# Siguino.net
KiCad netlist of a schematic drawn in EAGLE
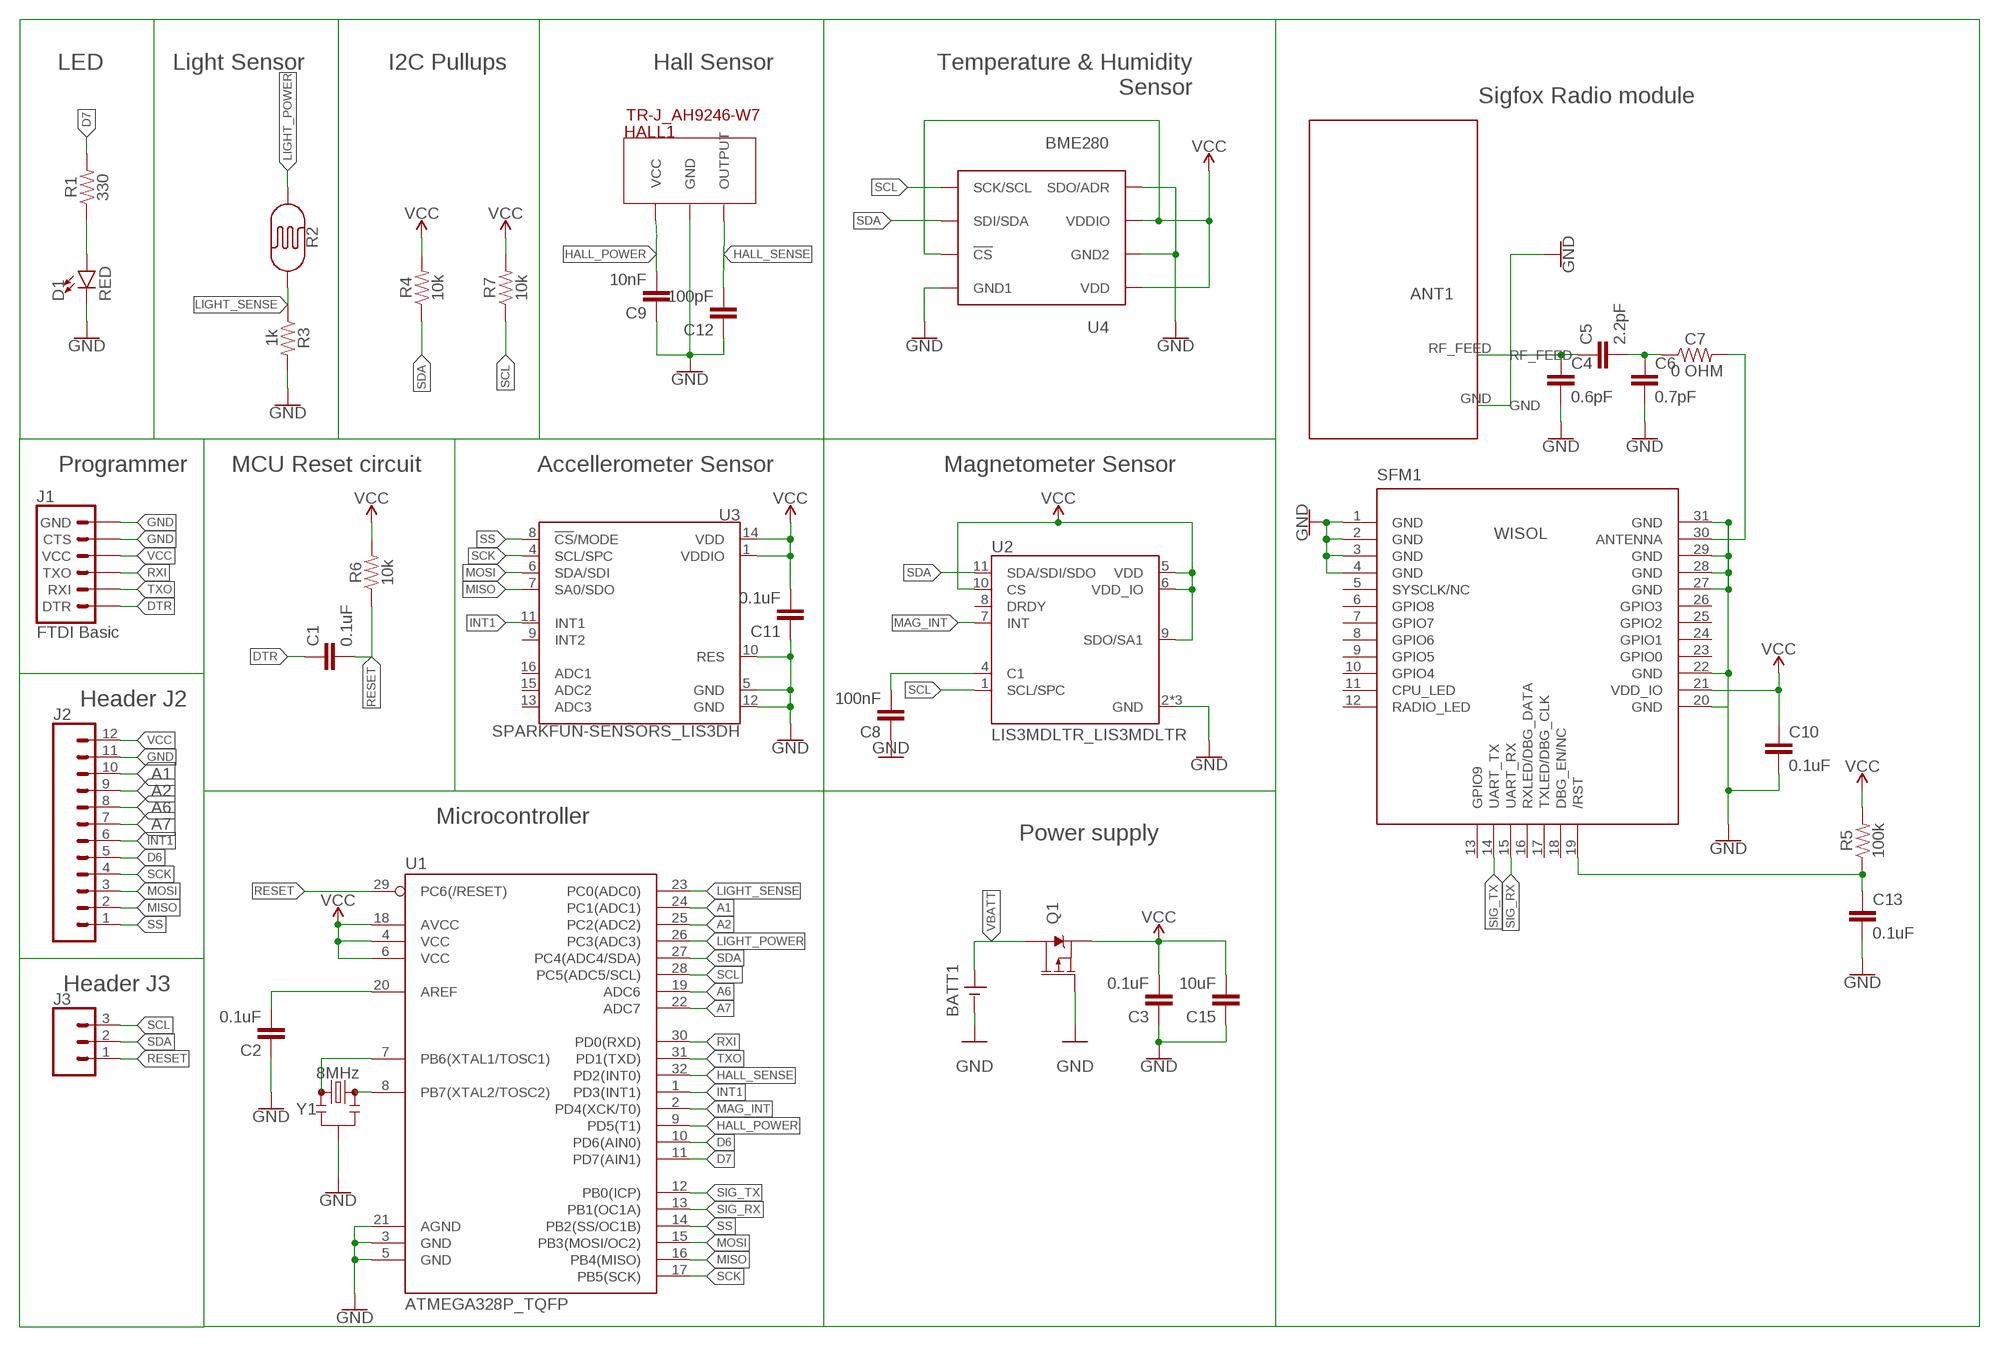
[diagram p0: schematic, sheet 1]

(export (version "E")
  (design (tool "Eeschema 10.0.6"))
  (components
    (comp (ref "ANT1")
      (value "PROOB471")
      (footprint "eagle-import:ONBOARD_SMD_2400")
      (libsource (lib "eagle-import") (part "PRO-OB-512ONBOARD"))
    )
    (comp (ref "BATT1")
      (value "SPARKFUN-BATTERIES_CR2-BATTERY-HOLDERPTH")
      (footprint "eagle-import:SPARKFUN-BATTERIES_BATTERYHOLDER-CR2")
      (libsource (lib "eagle-import") (part "SPARKFUN-BATTERIES_CR2-BATTERY-HOLDERPTH"))
    )
    (comp (ref "C1")
      (value "0.1uF")
      (footprint "eagle-import:0603")
      (libsource (lib "eagle-import") (part "0.1UF-0603-25V-5%"))
    )
    (comp (ref "C2")
      (value "0.1uF")
      (footprint "eagle-import:0603")
      (libsource (lib "eagle-import") (part "0.1UF-0603-25V-5%"))
    )
    (comp (ref "C3")
      (value "0.1uF")
      (footprint "eagle-import:0603")
      (libsource (lib "eagle-import") (part "0.1UF-0603-25V-5%"))
    )
    (comp (ref "C4")
      (value "0.6pF")
      (footprint "eagle-import:0402")
      (libsource (lib "eagle-import") (part "0.8PF-0402-50V-0.1PF"))
    )
    (comp (ref "C5")
      (value "2.2pF")
      (footprint "eagle-import:0402")
      (libsource (lib "eagle-import") (part "0.8PF-0402-50V-0.1PF"))
    )
    (comp (ref "C6")
      (value "0.7pF")
      (footprint "eagle-import:0402")
      (libsource (lib "eagle-import") (part "0.8PF-0402-50V-0.1PF"))
    )
    (comp (ref "C7")
      (value "0 OHM")
      (footprint "eagle-import:0402")
      (libsource (lib "eagle-import") (part "RESISTOR0402"))
    )
    (comp (ref "C8")
      (value "100nF")
      (footprint "eagle-import:0603")
      (libsource (lib "eagle-import") (part "0.1UF-0603-25V-5%"))
    )
    (comp (ref "C9")
      (value "10nF")
      (footprint "eagle-import:0603")
      (libsource (lib "eagle-import") (part "10NF-0603-50V-10%"))
    )
    (comp (ref "C10")
      (value "0.1uF")
      (footprint "eagle-import:0603")
      (libsource (lib "eagle-import") (part "0.1UF-0603-25V-(+80/-20%)"))
    )
    (comp (ref "C11")
      (value "0.1uF")
      (footprint "eagle-import:0603")
      (libsource (lib "eagle-import") (part "0.1UF-0603-25V-5%"))
    )
    (comp (ref "C12")
      (value "100pF")
      (footprint "eagle-import:0603")
      (libsource (lib "eagle-import") (part "100PF-0603-50V-5%"))
    )
    (comp (ref "C13")
      (value "0.1uF")
      (footprint "eagle-import:0603")
      (libsource (lib "eagle-import") (part "0.1UF-0603-25V-(+80/-20%)"))
    )
    (comp (ref "C15")
      (value "10uF")
      (footprint "eagle-import:0603")
      (libsource (lib "eagle-import") (part "10UF-0603-6.3V-20%"))
    )
    (comp (ref "D1")
      (value "RED")
      (footprint "eagle-import:LED-0603")
      (libsource (lib "eagle-import") (part "LED-RED0603"))
    )
    (comp (ref "HALL1")
      (value "TR-J_AH9246-W7")
      (footprint "eagle-import:TR-J_SC-59")
      (libsource (lib "eagle-import") (part "TR-J_AH9246-W7"))
    )
    (comp (ref "J1")
      (value "FTDI Basic")
      (footprint "eagle-import:1X06")
      (libsource (lib "eagle-import") (part "6_PIN_SERIAL_TARGET"))
    )
    (comp (ref "J2")
      (value "CONN_12")
      (footprint "eagle-import:1X12")
      (libsource (lib "eagle-import") (part "CONN_12"))
    )
    (comp (ref "J3")
      (value "CONN_03")
      (footprint "eagle-import:1X03")
      (libsource (lib "eagle-import") (part "CONN_03"))
    )
    (comp (ref "Q1")
      (value "MOSFET P-CH 20V 5.3A SOT-23")
      (footprint "eagle-import:SOT23-3")
      (libsource (lib "eagle-import") (part "MOSFET_PCHSI2323DDS"))
    )
    (comp (ref "R1")
      (value "330")
      (footprint "eagle-import:0603")
      (libsource (lib "eagle-import") (part "330OHM-0603-1/10W-1%"))
    )
    (comp (ref "R2")
      (value "PHOTOCELLPTH")
      (footprint "eagle-import:PHOTOCELL")
      (libsource (lib "eagle-import") (part "PHOTOCELLPTH"))
    )
    (comp (ref "R3")
      (value "1k")
      (footprint "eagle-import:0603")
      (libsource (lib "eagle-import") (part "1KOHM-0603-1/10W-1%"))
    )
    (comp (ref "R4")
      (value "10k")
      (footprint "eagle-import:0603")
      (libsource (lib "eagle-import") (part "10KOHM-0603-1/10W-1%"))
    )
    (comp (ref "R5")
      (value "100k")
      (footprint "eagle-import:0603")
      (libsource (lib "eagle-import") (part "100KOHM-0603-1/10W-1%"))
    )
    (comp (ref "R6")
      (value "10k")
      (footprint "eagle-import:0603")
      (libsource (lib "eagle-import") (part "10KOHM-0603-1/10W-1%"))
    )
    (comp (ref "R7")
      (value "10k")
      (footprint "eagle-import:0603")
      (libsource (lib "eagle-import") (part "10KOHM-0603-1/10W-1%"))
    )
    (comp (ref "SFM1")
      (value "WISOL_WSSFM10HANDSOLDER")
      (footprint "eagle-import:WISOL_WSSFM10")
      (libsource (lib "eagle-import") (part "WISOL_WSSFM10HANDSOLDER"))
    )
    (comp (ref "U1")
      (value "ATMEGA328P_TQFP")
      (footprint "eagle-import:TQFP32-08")
      (libsource (lib "eagle-import") (part "ATMEGA328P_TQFP"))
    )
    (comp (ref "U2")
      (value "LIS3MDLTR_LIS3MDLTR")
      (footprint "eagle-import:LIS3MDLTR_LGA12R50P4X4_200X200X100")
      (fields
        (field (name "DIGI-KEY_PART_NUMBER") "497-13892-1-ND")
        (field (name "MF") "STMicroelectronics")
        (field (name "MP") "LIS3MDLTR")
      )
      (libsource (lib "eagle-import") (part "LIS3MDLTR_LIS3MDLTR"))
    )
    (comp (ref "U3")
      (value "SPARKFUN-SENSORS_LIS3DH")
      (footprint "eagle-import:SPARKFUN-SENSORS_LGA-16-3X3")
      (libsource (lib "eagle-import") (part "SPARKFUN-SENSORS_LIS3DH"))
    )
    (comp (ref "U4")
      (value "BME280")
      (footprint "eagle-import:BME280COMPONENTLIBRARY_BME280_LGA")
      (libsource (lib "eagle-import") (part "BME280COMPONENTLIBRARY_BME280"))
    )
    (comp (ref "Y1")
      (value "8MHz")
      (footprint "eagle-import:RESONATOR-SMD-3.2X1.3")
      (libsource (lib "eagle-import") (part "RESONATOR-8MHZSMD_3.2X1.3"))
    )
  )
  (nets
    (net (code "1") (name "A1") (class "Default")
      (node (ref "J2") (pin "10") (pinfunction "10_10") (pintype "passive"))
      (node (ref "U1") (pin "24") (pinfunction "PC1(ADC1)_24") (pintype "bidirectional"))
    )
    (net (code "2") (name "A2") (class "Default")
      (node (ref "J2") (pin "9") (pinfunction "9_9") (pintype "passive"))
      (node (ref "U1") (pin "25") (pinfunction "PC2(ADC2)_25") (pintype "bidirectional"))
    )
    (net (code "3") (name "A6") (class "Default")
      (node (ref "J2") (pin "8") (pinfunction "8_8") (pintype "passive"))
      (node (ref "U1") (pin "19") (pinfunction "ADC6_19") (pintype "bidirectional"))
    )
    (net (code "4") (name "A7") (class "Default")
      (node (ref "J2") (pin "7") (pinfunction "7_7") (pintype "passive"))
      (node (ref "U1") (pin "22") (pinfunction "ADC7_22") (pintype "bidirectional"))
    )
    (net (code "5") (name "D6") (class "Default")
      (node (ref "J2") (pin "5") (pinfunction "5_5") (pintype "passive"))
      (node (ref "U1") (pin "10") (pinfunction "PD6(AIN0)_10") (pintype "bidirectional"))
    )
    (net (code "6") (name "D7") (class "Default")
      (node (ref "R1") (pin "2") (pinfunction "2_2") (pintype "passive"))
      (node (ref "U1") (pin "11") (pinfunction "PD7(AIN1)_11") (pintype "bidirectional"))
    )
    (net (code "7") (name "DTR") (class "Default")
      (node (ref "C1") (pin "1") (pinfunction "1_1") (pintype "passive"))
      (node (ref "J1") (pin "1") (pinfunction "DTR_1") (pintype "passive"))
    )
    (net (code "8") (name "GND") (class "Default")
      (node (ref "ANT1") (pin "GND") (pinfunction "GND_GND") (pintype "power_in"))
      (node (ref "BATT1") (pin "GND") (pinfunction "GND_GND") (pintype "power_in"))
      (node (ref "C10") (pin "2") (pinfunction "2_2") (pintype "passive"))
      (node (ref "C11") (pin "1") (pinfunction "1_1") (pintype "passive"))
      (node (ref "C12") (pin "1") (pinfunction "1_1") (pintype "passive"))
      (node (ref "C13") (pin "2") (pinfunction "2_2") (pintype "passive"))
      (node (ref "C15") (pin "1") (pinfunction "1_1") (pintype "passive"))
      (node (ref "C2") (pin "1") (pinfunction "1_1") (pintype "passive"))
      (node (ref "C3") (pin "1") (pinfunction "1_1") (pintype "passive"))
      (node (ref "C4") (pin "2") (pinfunction "2_2") (pintype "passive"))
      (node (ref "C6") (pin "2") (pinfunction "2_2") (pintype "passive"))
      (node (ref "C8") (pin "1") (pinfunction "1_1") (pintype "passive"))
      (node (ref "C9") (pin "1") (pinfunction "1_1") (pintype "passive"))
      (node (ref "D1") (pin "C") (pinfunction "C_C") (pintype "passive"))
      (node (ref "HALL1") (pin "3") (pinfunction "GND_3") (pintype "power_in"))
      (node (ref "J1") (pin "5") (pinfunction "CTS_5") (pintype "passive"))
      (node (ref "J1") (pin "6") (pinfunction "GND_6") (pintype "passive"))
      (node (ref "J2") (pin "11") (pinfunction "11_11") (pintype "passive"))
      (node (ref "Q1") (pin "1") (pinfunction "G_1") (pintype "bidirectional"))
      (node (ref "R3") (pin "2") (pinfunction "2_2") (pintype "passive"))
      (node (ref "SFM1") (pin "1") (pinfunction "GND_1") (pintype "power_in"))
      (node (ref "SFM1") (pin "2") (pinfunction "GND_2") (pintype "power_in"))
      (node (ref "SFM1") (pin "20") (pinfunction "GND_20") (pintype "power_in"))
      (node (ref "SFM1") (pin "22") (pinfunction "GND_22") (pintype "power_in"))
      (node (ref "SFM1") (pin "27") (pinfunction "GND_27") (pintype "power_in"))
      (node (ref "SFM1") (pin "28") (pinfunction "GND_28") (pintype "power_in"))
      (node (ref "SFM1") (pin "29") (pinfunction "GND_29") (pintype "power_in"))
      (node (ref "SFM1") (pin "3") (pinfunction "GND_3") (pintype "power_in"))
      (node (ref "SFM1") (pin "31") (pinfunction "GND_31") (pintype "power_in"))
      (node (ref "SFM1") (pin "4") (pinfunction "GND_4") (pintype "power_in"))
      (node (ref "U1") (pin "21") (pinfunction "AGND_21") (pintype "bidirectional"))
      (node (ref "U1") (pin "3") (pinfunction "GND_3") (pintype "bidirectional"))
      (node (ref "U1") (pin "5") (pinfunction "GND_5") (pintype "bidirectional"))
      (node (ref "U2") (pin "12") (pinfunction "GND_12") (pintype "power_in"))
      (node (ref "U2") (pin "2") (pinfunction "GND_2") (pintype "power_in"))
      (node (ref "U2") (pin "3") (pinfunction "GND_3") (pintype "power_in"))
      (node (ref "U3") (pin "10") (pinfunction "RES_10") (pintype "bidirectional"))
      (node (ref "U3") (pin "12") (pinfunction "GND_12") (pintype "bidirectional"))
      (node (ref "U3") (pin "5") (pinfunction "GND_5") (pintype "bidirectional"))
      (node (ref "U4") (pin "P$1") (pinfunction "GND1_P$1") (pintype "bidirectional"))
      (node (ref "U4") (pin "P$5") (pinfunction "SDO/ADR_P$5") (pintype "bidirectional"))
      (node (ref "U4") (pin "P$7") (pinfunction "GND2_P$7") (pintype "bidirectional"))
      (node (ref "Y1") (pin "2") (pinfunction "2_2") (pintype "passive"))
    )
    (net (code "9") (name "HALL_POWER") (class "Default")
      (node (ref "C9") (pin "2") (pinfunction "2_2") (pintype "passive"))
      (node (ref "HALL1") (pin "1") (pinfunction "VCC_1") (pintype "power_in"))
      (node (ref "U1") (pin "9") (pinfunction "PD5(T1)_9") (pintype "bidirectional"))
    )
    (net (code "10") (name "HALL_SENSE") (class "Default")
      (node (ref "C12") (pin "2") (pinfunction "2_2") (pintype "passive"))
      (node (ref "HALL1") (pin "2") (pinfunction "OUTPUT_2") (pintype "output"))
      (node (ref "U1") (pin "32") (pinfunction "PD2(INT0)_32") (pintype "bidirectional"))
    )
    (net (code "11") (name "INT1") (class "Default")
      (node (ref "J2") (pin "6") (pinfunction "6_6") (pintype "passive"))
      (node (ref "U1") (pin "1") (pinfunction "PD3(INT1)_1") (pintype "bidirectional"))
      (node (ref "U3") (pin "11") (pinfunction "INT1_11") (pintype "bidirectional"))
    )
    (net (code "12") (name "LIGHT_POWER") (class "Default")
      (node (ref "R2") (pin "1") (pinfunction "P$1_1") (pintype "bidirectional"))
      (node (ref "U1") (pin "26") (pinfunction "PC3(ADC3)_26") (pintype "bidirectional"))
    )
    (net (code "13") (name "LIGHT_SENSE") (class "Default")
      (node (ref "R2") (pin "2") (pinfunction "P$2_2") (pintype "bidirectional"))
      (node (ref "R3") (pin "1") (pinfunction "1_1") (pintype "passive"))
      (node (ref "U1") (pin "23") (pinfunction "PC0(ADC0)_23") (pintype "bidirectional"))
    )
    (net (code "14") (name "MAG_INT") (class "Default")
      (node (ref "U1") (pin "2") (pinfunction "PD4(XCK/T0)_2") (pintype "bidirectional"))
      (node (ref "U2") (pin "7") (pinfunction "INT_7") (pintype "input"))
    )
    (net (code "15") (name "MISO") (class "Default")
      (node (ref "J2") (pin "2") (pinfunction "2_2") (pintype "passive"))
      (node (ref "U1") (pin "16") (pinfunction "PB4(MISO)_16") (pintype "bidirectional"))
      (node (ref "U3") (pin "7") (pinfunction "SA0/SDO_7") (pintype "bidirectional"))
    )
    (net (code "16") (name "MOSI") (class "Default")
      (node (ref "J2") (pin "3") (pinfunction "3_3") (pintype "passive"))
      (node (ref "U1") (pin "15") (pinfunction "PB3(MOSI/OC2)_15") (pintype "bidirectional"))
      (node (ref "U3") (pin "6") (pinfunction "SDA/SDI_6") (pintype "bidirectional"))
    )
    (net (code "17") (name "Net-(ANT1-PadRF_FEED)") (class "Default")
      (node (ref "ANT1") (pin "RF_FEED") (pinfunction "RF_FEED_RF_FEED") (pintype "input"))
      (node (ref "C4") (pin "1") (pinfunction "1_1") (pintype "passive"))
      (node (ref "C5") (pin "1") (pinfunction "1_1") (pintype "passive"))
    )
    (net (code "18") (name "Net-(C5-Pad2)") (class "Default")
      (node (ref "C5") (pin "2") (pinfunction "2_2") (pintype "passive"))
      (node (ref "C6") (pin "1") (pinfunction "1_1") (pintype "passive"))
      (node (ref "C7") (pin "1") (pinfunction "1_1") (pintype "passive"))
    )
    (net (code "19") (name "Net-(D1-PadA)") (class "Default")
      (node (ref "D1") (pin "A") (pinfunction "A_A") (pintype "passive"))
      (node (ref "R1") (pin "1") (pinfunction "1_1") (pintype "passive"))
    )
    (net (code "20") (name "Net-(SFM1-ANTENNA)") (class "Default")
      (node (ref "C7") (pin "2") (pinfunction "2_2") (pintype "passive"))
      (node (ref "SFM1") (pin "30") (pinfunction "ANTENNA_30") (pintype "output"))
    )
    (net (code "21") (name "Net-(SFM1-{slash}RST)") (class "Default")
      (node (ref "C13") (pin "1") (pinfunction "1_1") (pintype "passive"))
      (node (ref "R5") (pin "1") (pinfunction "1_1") (pintype "passive"))
      (node (ref "SFM1") (pin "19") (pinfunction "/RST_19") (pintype "input"))
    )
    (net (code "22") (name "Net-(U1-AREF)") (class "Default")
      (node (ref "C2") (pin "2") (pinfunction "2_2") (pintype "passive"))
      (node (ref "U1") (pin "20") (pinfunction "AREF_20") (pintype "bidirectional"))
    )
    (net (code "23") (name "Net-(U1-PB6(XTAL1{slash}TOSC1))") (class "Default")
      (node (ref "U1") (pin "7") (pinfunction "PB6(XTAL1/TOSC1)_7") (pintype "bidirectional"))
      (node (ref "Y1") (pin "1") (pinfunction "1_1") (pintype "passive"))
    )
    (net (code "24") (name "Net-(U1-PB7(XTAL2{slash}TOSC2))") (class "Default")
      (node (ref "U1") (pin "8") (pinfunction "PB7(XTAL2/TOSC2)_8") (pintype "bidirectional"))
      (node (ref "Y1") (pin "3") (pinfunction "3_3") (pintype "passive"))
    )
    (net (code "25") (name "Net-(U2-C1)") (class "Default")
      (node (ref "C8") (pin "2") (pinfunction "2_2") (pintype "passive"))
      (node (ref "U2") (pin "4") (pinfunction "C1_4") (pintype "bidirectional"))
    )
    (net (code "26") (name "RESET") (class "Default")
      (node (ref "C1") (pin "2") (pinfunction "2_2") (pintype "passive"))
      (node (ref "J3") (pin "1") (pinfunction "1_1") (pintype "passive"))
      (node (ref "R6") (pin "1") (pinfunction "1_1") (pintype "passive"))
      (node (ref "U1") (pin "29") (pinfunction "PC6(/RESET)_29") (pintype "bidirectional"))
    )
    (net (code "27") (name "RXI") (class "Default")
      (node (ref "J1") (pin "3") (pinfunction "TXO_3") (pintype "passive"))
      (node (ref "U1") (pin "30") (pinfunction "PD0(RXD)_30") (pintype "bidirectional"))
    )
    (net (code "28") (name "SCK") (class "Default")
      (node (ref "J2") (pin "4") (pinfunction "4_4") (pintype "passive"))
      (node (ref "U1") (pin "17") (pinfunction "PB5(SCK)_17") (pintype "bidirectional"))
      (node (ref "U3") (pin "4") (pinfunction "SCL/SPC_4") (pintype "bidirectional"))
    )
    (net (code "29") (name "SCL") (class "Default")
      (node (ref "J3") (pin "3") (pinfunction "3_3") (pintype "passive"))
      (node (ref "R7") (pin "1") (pinfunction "1_1") (pintype "passive"))
      (node (ref "U1") (pin "28") (pinfunction "PC5(ADC5/SCL)_28") (pintype "bidirectional"))
      (node (ref "U2") (pin "1") (pinfunction "SCL/SPC_1") (pintype "bidirectional"))
      (node (ref "U4") (pin "P$4") (pinfunction "SCK/SCL_P$4") (pintype "bidirectional"))
    )
    (net (code "30") (name "SDA") (class "Default")
      (node (ref "J3") (pin "2") (pinfunction "2_2") (pintype "passive"))
      (node (ref "R4") (pin "1") (pinfunction "1_1") (pintype "passive"))
      (node (ref "U1") (pin "27") (pinfunction "PC4(ADC4/SDA)_27") (pintype "bidirectional"))
      (node (ref "U2") (pin "11") (pinfunction "SDA/SDI/SDO_11") (pintype "input"))
      (node (ref "U4") (pin "P$3") (pinfunction "SDI/SDA_P$3") (pintype "bidirectional"))
    )
    (net (code "31") (name "SIG_RX") (class "Default")
      (node (ref "SFM1") (pin "15") (pinfunction "UART_RX_15") (pintype "input"))
      (node (ref "U1") (pin "13") (pinfunction "PB1(OC1A)_13") (pintype "bidirectional"))
    )
    (net (code "32") (name "SIG_TX") (class "Default")
      (node (ref "SFM1") (pin "14") (pinfunction "UART_TX_14") (pintype "output"))
      (node (ref "U1") (pin "12") (pinfunction "PB0(ICP)_12") (pintype "bidirectional"))
    )
    (net (code "33") (name "SS") (class "Default")
      (node (ref "J2") (pin "1") (pinfunction "1_1") (pintype "passive"))
      (node (ref "U1") (pin "14") (pinfunction "PB2(SS/OC1B)_14") (pintype "bidirectional"))
      (node (ref "U3") (pin "8") (pinfunction "~{CS}/MODE_8") (pintype "bidirectional"))
    )
    (net (code "34") (name "TXO") (class "Default")
      (node (ref "J1") (pin "2") (pinfunction "RXI_2") (pintype "passive"))
      (node (ref "U1") (pin "31") (pinfunction "PD1(TXD)_31") (pintype "bidirectional"))
    )
    (net (code "35") (name "VBATT") (class "Default")
      (node (ref "BATT1") (pin "VBATT") (pinfunction "VBATT_VBATT") (pintype "power_in"))
      (node (ref "Q1") (pin "3") (pinfunction "D_3") (pintype "bidirectional"))
    )
    (net (code "36") (name "VCC") (class "Default")
      (node (ref "C10") (pin "1") (pinfunction "1_1") (pintype "passive"))
      (node (ref "C11") (pin "2") (pinfunction "2_2") (pintype "passive"))
      (node (ref "C15") (pin "2") (pinfunction "2_2") (pintype "passive"))
      (node (ref "C3") (pin "2") (pinfunction "2_2") (pintype "passive"))
      (node (ref "J1") (pin "4") (pinfunction "VCC_4") (pintype "passive"))
      (node (ref "J2") (pin "12") (pinfunction "12_12") (pintype "passive"))
      (node (ref "Q1") (pin "2") (pinfunction "S_2") (pintype "bidirectional"))
      (node (ref "R4") (pin "2") (pinfunction "2_2") (pintype "passive"))
      (node (ref "R5") (pin "2") (pinfunction "2_2") (pintype "passive"))
      (node (ref "R6") (pin "2") (pinfunction "2_2") (pintype "passive"))
      (node (ref "R7") (pin "2") (pinfunction "2_2") (pintype "passive"))
      (node (ref "SFM1") (pin "21") (pinfunction "VDD_IO_21") (pintype "power_in"))
      (node (ref "U1") (pin "18") (pinfunction "AVCC_18") (pintype "bidirectional"))
      (node (ref "U1") (pin "4") (pinfunction "VCC_4") (pintype "bidirectional"))
      (node (ref "U1") (pin "6") (pinfunction "VCC_6") (pintype "bidirectional"))
      (node (ref "U2") (pin "10") (pinfunction "CS_10") (pintype "input"))
      (node (ref "U2") (pin "5") (pinfunction "VDD_5") (pintype "power_in"))
      (node (ref "U2") (pin "6") (pinfunction "VDD_IO_6") (pintype "power_in"))
      (node (ref "U2") (pin "9") (pinfunction "SDO/SA1_9") (pintype "output"))
      (node (ref "U3") (pin "1") (pinfunction "VDDIO_1") (pintype "bidirectional"))
      (node (ref "U3") (pin "14") (pinfunction "VDD_14") (pintype "bidirectional"))
      (node (ref "U4") (pin "P$2") (pinfunction "~{CS}_P$2") (pintype "bidirectional"))
      (node (ref "U4") (pin "P$6") (pinfunction "VDDIO_P$6") (pintype "bidirectional"))
      (node (ref "U4") (pin "P$8") (pinfunction "VDD_P$8") (pintype "bidirectional"))
    )
    (net (code "37") (name "unconnected-(SFM1-CPU_LED-Pad11)") (class "Default")
      (node (ref "SFM1") (pin "11") (pinfunction "CPU_LED_11") (pintype "output"))
    )
    (net (code "38") (name "unconnected-(SFM1-DBG_EN{slash}NC-Pad18)") (class "Default")
      (node (ref "SFM1") (pin "18") (pinfunction "DBG_EN/NC_18") (pintype "no_connect"))
    )
    (net (code "39") (name "unconnected-(SFM1-GPIO0-Pad23)") (class "Default")
      (node (ref "SFM1") (pin "23") (pinfunction "GPIO0_23") (pintype "bidirectional"))
    )
    (net (code "40") (name "unconnected-(SFM1-GPIO1-Pad24)") (class "Default")
      (node (ref "SFM1") (pin "24") (pinfunction "GPIO1_24") (pintype "bidirectional"))
    )
    (net (code "41") (name "unconnected-(SFM1-GPIO2-Pad25)") (class "Default")
      (node (ref "SFM1") (pin "25") (pinfunction "GPIO2_25") (pintype "bidirectional"))
    )
    (net (code "42") (name "unconnected-(SFM1-GPIO3-Pad26)") (class "Default")
      (node (ref "SFM1") (pin "26") (pinfunction "GPIO3_26") (pintype "bidirectional"))
    )
    (net (code "43") (name "unconnected-(SFM1-GPIO4-Pad10)") (class "Default")
      (node (ref "SFM1") (pin "10") (pinfunction "GPIO4_10") (pintype "bidirectional"))
    )
    (net (code "44") (name "unconnected-(SFM1-GPIO5-Pad9)") (class "Default")
      (node (ref "SFM1") (pin "9") (pinfunction "GPIO5_9") (pintype "bidirectional"))
    )
    (net (code "45") (name "unconnected-(SFM1-GPIO6-Pad8)") (class "Default")
      (node (ref "SFM1") (pin "8") (pinfunction "GPIO6_8") (pintype "bidirectional"))
    )
    (net (code "46") (name "unconnected-(SFM1-GPIO7-Pad7)") (class "Default")
      (node (ref "SFM1") (pin "7") (pinfunction "GPIO7_7") (pintype "bidirectional"))
    )
    (net (code "47") (name "unconnected-(SFM1-GPIO8-Pad6)") (class "Default")
      (node (ref "SFM1") (pin "6") (pinfunction "GPIO8_6") (pintype "bidirectional"))
    )
    (net (code "48") (name "unconnected-(SFM1-GPIO9-Pad13)") (class "Default")
      (node (ref "SFM1") (pin "13") (pinfunction "GPIO9_13") (pintype "bidirectional"))
    )
    (net (code "49") (name "unconnected-(SFM1-RADIO_LED-Pad12)") (class "Default")
      (node (ref "SFM1") (pin "12") (pinfunction "RADIO_LED_12") (pintype "output"))
    )
    (net (code "50") (name "unconnected-(SFM1-RXLED{slash}DBG_DATA-Pad16)") (class "Default")
      (node (ref "SFM1") (pin "16") (pinfunction "RXLED/DBG_DATA_16") (pintype "output"))
    )
    (net (code "51") (name "unconnected-(SFM1-SYSCLK{slash}NC-Pad5)") (class "Default")
      (node (ref "SFM1") (pin "5") (pinfunction "SYSCLK/NC_5") (pintype "no_connect"))
    )
    (net (code "52") (name "unconnected-(SFM1-TXLED{slash}DBG_CLK-Pad17)") (class "Default")
      (node (ref "SFM1") (pin "17") (pinfunction "TXLED/DBG_CLK_17") (pintype "output"))
    )
    (net (code "53") (name "unconnected-(U2-DRDY-Pad8)") (class "Default")
      (node (ref "U2") (pin "8") (pinfunction "DRDY_8") (pintype "input"))
    )
    (net (code "54") (name "unconnected-(U3-ADC1-Pad16)") (class "Default")
      (node (ref "U3") (pin "16") (pinfunction "ADC1_16") (pintype "bidirectional"))
    )
    (net (code "55") (name "unconnected-(U3-ADC2-Pad15)") (class "Default")
      (node (ref "U3") (pin "15") (pinfunction "ADC2_15") (pintype "bidirectional"))
    )
    (net (code "56") (name "unconnected-(U3-ADC3-Pad13)") (class "Default")
      (node (ref "U3") (pin "13") (pinfunction "ADC3_13") (pintype "bidirectional"))
    )
    (net (code "57") (name "unconnected-(U3-INT2-Pad9)") (class "Default")
      (node (ref "U3") (pin "9") (pinfunction "INT2_9") (pintype "bidirectional"))
    )
  )
)
